# BLDC-CONNECTORS.net
KiCad netlist of a schematic drawn in Altium Designer
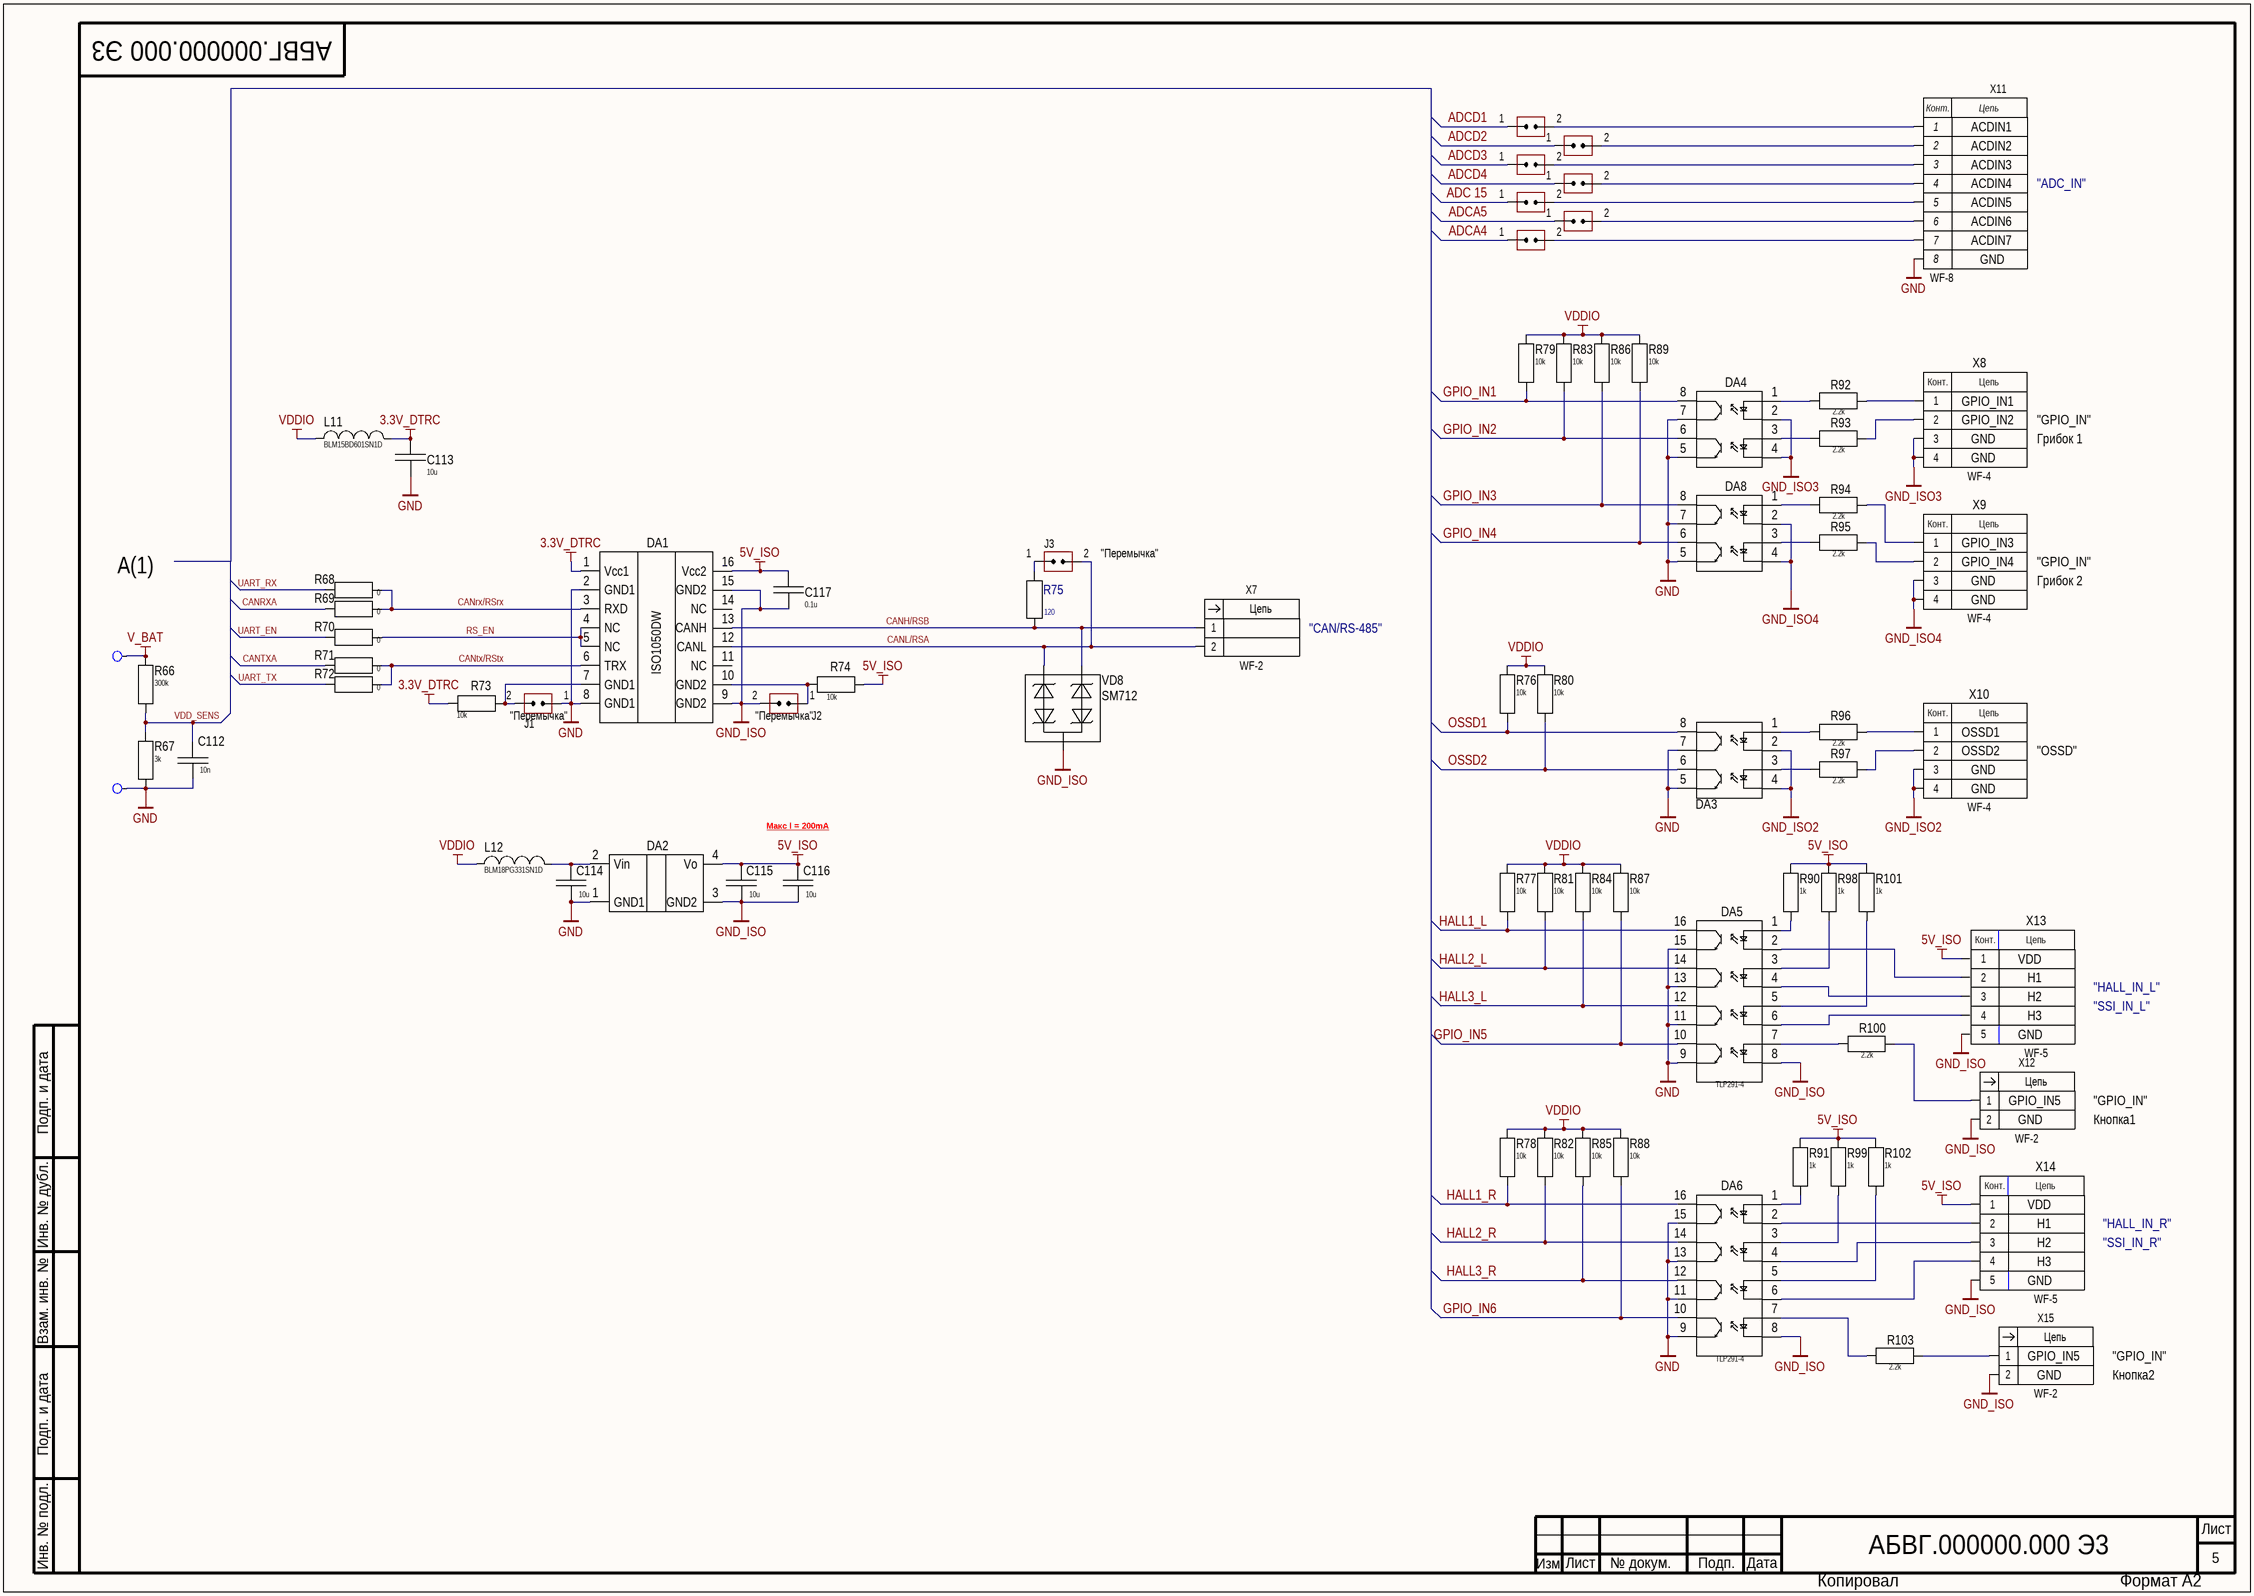
[diagram p0: BLDC-CONNECTORS.SchDoc]

(export (version "E")
  (design (tool "Eeschema 10.0.6"))
  (components
    (comp (ref "C112")
      (value "10n")
      (footprint "CAP: 0402")
      (fields
        (field (name "VOLTAGE") "10V")
        (field (name "PARTNUMBER") "C0402C104K8PAC")
        (field (name "MANUFACTURER") "Kemet")
      )
      (libsource (lib "Fider_Board_Lib") (part "CAP 0402"))
    )
    (comp (ref "C113")
      (value "10u")
      (footprint "CAP: 0402")
      (fields (field (name "VOLTAGE") "6.3V") (field (name "PARTNUMBER") "CC0402MRX5R5BB106"))
      (libsource (lib "Fider_Board_Lib") (part "CAP 0402"))
    )
    (comp (ref "C114")
      (value "10u")
      (footprint "CAP: 0402")
      (fields (field (name "VOLTAGE") "6.3V") (field (name "PARTNUMBER") "CC0402MRX5R5BB106"))
      (libsource (lib "Fider_Board_Lib") (part "CAP 0402"))
    )
    (comp (ref "C115")
      (value "10u")
      (footprint "CAP: 0402")
      (fields (field (name "VOLTAGE") "6.3V") (field (name "PARTNUMBER") "CC0402MRX5R5BB106"))
      (libsource (lib "Fider_Board_Lib") (part "CAP 0402"))
    )
    (comp (ref "C116")
      (value "10u")
      (footprint "CAP: 0402")
      (fields (field (name "VOLTAGE") "6.3V") (field (name "PARTNUMBER") "CC0402MRX5R5BB106"))
      (libsource (lib "Fider_Board_Lib") (part "CAP 0402"))
    )
    (comp (ref "C117")
      (value "0.1u")
      (footprint "CAP: 0402")
      (fields
        (field (name "VOLTAGE") "10V")
        (field (name "PARTNUMBER") "C0402C104K8PAC")
        (field (name "MANUFACTURER") "Kemet")
      )
      (libsource (lib "Fider_Board_Lib") (part "CAP 0402"))
    )
    (comp (ref "DA1")
      (value "ISO1050DW")
      (footprint "SOIC-16-300-1.27")
      (description "Isolated CAN Trcvr 5kV RMS")
      (fields (field (name "PARTNUMBER") "ISO1050DW"))
      (libsource (lib "BKM_SCH_Lib") (part "ISO1050DW"))
    )
    (comp (ref "DA2")
      (value "ROE-3.305S")
      (footprint "ROE-3.305S")
      (description "Isol DC/DC 3 to 5V 0.2A")
      (fields (field (name "PARTNUMBER") "TSR 1"))
      (libsource (lib "BKM_SCH_Lib") (part "ROE-3.305S"))
    )
    (comp (ref "DA3")
      (value "MOCD207R2M")
      (footprint "8-SOIC")
      (libsource (lib "BKM_SCH_Lib") (part "MOCD207R2M"))
    )
    (comp (ref "DA4")
      (value "MOCD207R2M")
      (footprint "8-SOIC")
      (libsource (lib "BKM_SCH_Lib") (part "MOCD207R2M"))
    )
    (comp (ref "DA5")
      (value "TLP291-4")
      (footprint "16-SO")
      (fields (field (name "PARTNUMBER") "TLP291-4(GB.E)"))
      (libsource (lib "BKM_SCH_Lib") (part "TLP291-4(GB.E)"))
    )
    (comp (ref "DA6")
      (value "TLP291-4")
      (footprint "16-SO")
      (fields (field (name "PARTNUMBER") "TLP291-4(GB.E)"))
      (libsource (lib "BKM_SCH_Lib") (part "TLP291-4(GB.E)"))
    )
    (comp (ref "DA8")
      (value "MOCD207R2M")
      (footprint "8-SOIC")
      (libsource (lib "BKM_SCH_Lib") (part "MOCD207R2M"))
    )
    (comp (ref "J1")
      (value "~")
      (footprint "CustomCase:CON: JUMPER x1")
      (fields (field (name "COMMENTTEXT") "\"Перемычка\""))
      (libsource (lib "Connector") (part "Jumper_single"))
    )
    (comp (ref "J2")
      (value "~")
      (footprint "CustomCase:CON: JUMPER x1")
      (fields (field (name "COMMENTTEXT") "\"Перемычка\""))
      (libsource (lib "Connector") (part "Jumper_single"))
    )
    (comp (ref "J3")
      (value "~")
      (footprint "CustomCase:CON: JUMPER x1")
      (fields (field (name "COMMENTTEXT") "\"Перемычка\""))
      (libsource (lib "") (part "Jumper_single_1"))
    )
    (comp (ref "J4")
      (value "~")
      (footprint "CustomCase:CON: JUMPER x1")
      (libsource (lib "") (part "Jumper_single_1"))
    )
    (comp (ref "J5")
      (value "~")
      (footprint "CustomCase:CON: JUMPER x1")
      (libsource (lib "") (part "Jumper_single_1"))
    )
    (comp (ref "J6")
      (value "~")
      (footprint "CustomCase:CON: JUMPER x1")
      (libsource (lib "") (part "Jumper_single_1"))
    )
    (comp (ref "J7")
      (value "~")
      (footprint "CustomCase:CON: JUMPER x1")
      (libsource (lib "") (part "Jumper_single_1"))
    )
    (comp (ref "J8")
      (value "~")
      (footprint "CustomCase:CON: JUMPER x1")
      (libsource (lib "") (part "Jumper_single_1"))
    )
    (comp (ref "J9")
      (value "~")
      (footprint "CustomCase:CON: JUMPER x1")
      (libsource (lib "") (part "Jumper_single_1"))
    )
    (comp (ref "J10")
      (value "~")
      (footprint "CustomCase:CON: JUMPER x1")
      (libsource (lib "") (part "Jumper_single_1"))
    )
    (comp (ref "L11")
      (value "BLM15BD601SN1D")
      (footprint "IND: 0402")
      (libsource (lib "Fider_Board_Lib") (part "BLM15BD601SN1D"))
    )
    (comp (ref "L12")
      (value "BLM18PG331SN1D")
      (footprint "IND: 0603")
      (libsource (lib "Fider_Board_Lib") (part "BLM18PG331SN1D"))
    )
    (comp (ref "R66")
      (value "300k")
      (footprint "RES: 0402")
      (fields (field (name "TOLERANCE") "1%"))
      (libsource (lib "BKM_SCH_Lib") (part "RES 0402"))
    )
    (comp (ref "R67")
      (value "3k")
      (footprint "RES: 0402")
      (fields (field (name "TOLERANCE") "1%"))
      (libsource (lib "BKM_SCH_Lib") (part "RES 0402"))
    )
    (comp (ref "R68")
      (value "0")
      (footprint "RES: 0402")
      (fields (field (name "TOLERANCE") "1%"))
      (libsource (lib "BKM_SCH_Lib") (part "RES 0402"))
    )
    (comp (ref "R69")
      (value "0")
      (footprint "RES: 0402")
      (fields (field (name "TOLERANCE") "1%"))
      (libsource (lib "BKM_SCH_Lib") (part "RES 0402"))
    )
    (comp (ref "R70")
      (value "0")
      (footprint "RES: 0402")
      (fields (field (name "TOLERANCE") "1%"))
      (libsource (lib "BKM_SCH_Lib") (part "RES 0402"))
    )
    (comp (ref "R71")
      (value "0")
      (footprint "RES: 0402")
      (fields (field (name "TOLERANCE") "1%"))
      (libsource (lib "BKM_SCH_Lib") (part "RES 0402"))
    )
    (comp (ref "R72")
      (value "0")
      (footprint "RES: 0402")
      (fields (field (name "TOLERANCE") "1%"))
      (libsource (lib "BKM_SCH_Lib") (part "RES 0402"))
    )
    (comp (ref "R73")
      (value "10k")
      (footprint "RES: 0402")
      (fields (field (name "TOLERANCE") "1%"))
      (libsource (lib "BKM_SCH_Lib") (part "RES 0402"))
    )
    (comp (ref "R74")
      (value "10k")
      (footprint "RES: 0402")
      (fields (field (name "TOLERANCE") "1%"))
      (libsource (lib "BKM_SCH_Lib") (part "RES 0402"))
    )
    (comp (ref "R75")
      (value "120")
      (footprint "RES: 0603")
      (fields (field (name "PARTNUMBER") "CRCW0603120RFKEAHP"))
      (libsource (lib "Fider_Board_Lib") (part "RES 0603"))
    )
    (comp (ref "R76")
      (value "10k")
      (footprint "RES: 0402")
      (fields (field (name "TOLERANCE") "1%"))
      (libsource (lib "BKM_SCH_Lib") (part "RES 0402"))
    )
    (comp (ref "R77")
      (value "10k")
      (footprint "RES: 0402")
      (fields (field (name "TOLERANCE") "1%"))
      (libsource (lib "BKM_SCH_Lib") (part "RES 0402"))
    )
    (comp (ref "R78")
      (value "10k")
      (footprint "RES: 0402")
      (fields (field (name "TOLERANCE") "1%"))
      (libsource (lib "BKM_SCH_Lib") (part "RES 0402"))
    )
    (comp (ref "R79")
      (value "10k")
      (footprint "RES: 0402")
      (fields (field (name "TOLERANCE") "1%"))
      (libsource (lib "BKM_SCH_Lib") (part "RES 0402"))
    )
    (comp (ref "R80")
      (value "10k")
      (footprint "RES: 0402")
      (fields (field (name "TOLERANCE") "1%"))
      (libsource (lib "BKM_SCH_Lib") (part "RES 0402"))
    )
    (comp (ref "R81")
      (value "10k")
      (footprint "RES: 0402")
      (fields (field (name "TOLERANCE") "1%"))
      (libsource (lib "BKM_SCH_Lib") (part "RES 0402"))
    )
    (comp (ref "R82")
      (value "10k")
      (footprint "RES: 0402")
      (fields (field (name "TOLERANCE") "1%"))
      (libsource (lib "BKM_SCH_Lib") (part "RES 0402"))
    )
    (comp (ref "R83")
      (value "10k")
      (footprint "RES: 0402")
      (fields (field (name "TOLERANCE") "1%"))
      (libsource (lib "BKM_SCH_Lib") (part "RES 0402"))
    )
    (comp (ref "R84")
      (value "10k")
      (footprint "RES: 0402")
      (fields (field (name "TOLERANCE") "1%"))
      (libsource (lib "BKM_SCH_Lib") (part "RES 0402"))
    )
    (comp (ref "R85")
      (value "10k")
      (footprint "RES: 0402")
      (fields (field (name "TOLERANCE") "1%"))
      (libsource (lib "BKM_SCH_Lib") (part "RES 0402"))
    )
    (comp (ref "R86")
      (value "10k")
      (footprint "RES: 0402")
      (fields (field (name "TOLERANCE") "1%"))
      (libsource (lib "BKM_SCH_Lib") (part "RES 0402"))
    )
    (comp (ref "R87")
      (value "10k")
      (footprint "RES: 0402")
      (fields (field (name "TOLERANCE") "1%"))
      (libsource (lib "BKM_SCH_Lib") (part "RES 0402"))
    )
    (comp (ref "R88")
      (value "10k")
      (footprint "RES: 0402")
      (fields (field (name "TOLERANCE") "1%"))
      (libsource (lib "BKM_SCH_Lib") (part "RES 0402"))
    )
    (comp (ref "R89")
      (value "10k")
      (footprint "RES: 0402")
      (fields (field (name "TOLERANCE") "1%"))
      (libsource (lib "BKM_SCH_Lib") (part "RES 0402"))
    )
    (comp (ref "R90")
      (value "1k")
      (footprint "RES: 0402")
      (fields (field (name "TOLERANCE") "1%"))
      (libsource (lib "BKM_SCH_Lib") (part "RES 0402"))
    )
    (comp (ref "R91")
      (value "1k")
      (footprint "RES: 0402")
      (fields (field (name "TOLERANCE") "1%"))
      (libsource (lib "BKM_SCH_Lib") (part "RES 0402"))
    )
    (comp (ref "R92")
      (value "2.2k")
      (footprint "RES: 0402")
      (fields (field (name "TOLERANCE") "1%"))
      (libsource (lib "BKM_SCH_Lib") (part "RES 0402"))
    )
    (comp (ref "R93")
      (value "2.2k")
      (footprint "RES: 0402")
      (fields (field (name "TOLERANCE") "1%"))
      (libsource (lib "BKM_SCH_Lib") (part "RES 0402"))
    )
    (comp (ref "R94")
      (value "2.2k")
      (footprint "RES: 0402")
      (fields (field (name "TOLERANCE") "1%"))
      (libsource (lib "BKM_SCH_Lib") (part "RES 0402"))
    )
    (comp (ref "R95")
      (value "2.2k")
      (footprint "RES: 0402")
      (fields (field (name "TOLERANCE") "1%"))
      (libsource (lib "BKM_SCH_Lib") (part "RES 0402"))
    )
    (comp (ref "R96")
      (value "2.2k")
      (footprint "RES: 0402")
      (fields (field (name "TOLERANCE") "1%"))
      (libsource (lib "BKM_SCH_Lib") (part "RES 0402"))
    )
    (comp (ref "R97")
      (value "2.2k")
      (footprint "RES: 0402")
      (fields (field (name "TOLERANCE") "1%"))
      (libsource (lib "BKM_SCH_Lib") (part "RES 0402"))
    )
    (comp (ref "R98")
      (value "1k")
      (footprint "RES: 0402")
      (fields (field (name "TOLERANCE") "1%"))
      (libsource (lib "BKM_SCH_Lib") (part "RES 0402"))
    )
    (comp (ref "R99")
      (value "1k")
      (footprint "RES: 0402")
      (fields (field (name "TOLERANCE") "1%"))
      (libsource (lib "BKM_SCH_Lib") (part "RES 0402"))
    )
    (comp (ref "R100")
      (value "2.2k")
      (footprint "RES: 0402")
      (fields (field (name "TOLERANCE") "1%"))
      (libsource (lib "BKM_SCH_Lib") (part "RES 0402"))
    )
    (comp (ref "R101")
      (value "1k")
      (footprint "RES: 0402")
      (fields (field (name "TOLERANCE") "1%"))
      (libsource (lib "BKM_SCH_Lib") (part "RES 0402"))
    )
    (comp (ref "R102")
      (value "1k")
      (footprint "RES: 0402")
      (fields (field (name "TOLERANCE") "1%"))
      (libsource (lib "BKM_SCH_Lib") (part "RES 0402"))
    )
    (comp (ref "R103")
      (value "2.2k")
      (footprint "RES: 0402")
      (fields (field (name "TOLERANCE") "1%"))
      (libsource (lib "BKM_SCH_Lib") (part "RES 0402"))
    )
    (comp (ref "T1")
      (value "TestPoint PWR")
      (footprint "CON: DJ617-6.3 (TA-MR1)")
      (libsource (lib "BKM_SCH_Lib") (part "TestPoint PWR"))
    )
    (comp (ref "T2")
      (value "TestPoint PWR")
      (footprint "CON: DJ617-6.3 (TA-MR1)")
      (libsource (lib "BKM_SCH_Lib") (part "TestPoint PWR"))
    )
    (comp (ref "VD8")
      (value "SM712")
      (footprint "SOT-23-3")
      (fields (field (name "PARTNUMBER") "SM712-02HTG"))
      (libsource (lib "Fider_Board_Lib") (part "SM712"))
    )
    (comp (ref "X7")
      (value "WF-2")
      (footprint "WF-2")
      (fields (field (name "PARTNUMBER") "Вилка WF-2 «Zhenqin»"))
      (libsource (lib "connectors") (part "WF-2"))
    )
    (comp (ref "X8") (value "WF-4") (footprint "WF-4") (libsource (lib "connectors") (part "WF-4_T")))
    (comp (ref "X9") (value "WF-4") (footprint "WF-4") (libsource (lib "connectors") (part "WF-4_T")))
    (comp (ref "X10") (value "WF-4") (footprint "WF-4") (libsource (lib "connectors") (part "WF-4_T")))
    (comp (ref "X11")
      (value "WF-8")
      (footprint "WF-8")
      (fields (field (name "PARTNUMBER") "Вилка WF-8 «Zhenqin»"))
      (libsource (lib "connectors") (part "WF-8"))
    )
    (comp (ref "X12")
      (value "WF-2")
      (footprint "WF-2")
      (fields (field (name "PARTNUMBER") "Вилка WF-2 «Zhenqin»"))
      (libsource (lib "connectors") (part "WF-2"))
    )
    (comp (ref "X13")
      (value "WF-5")
      (footprint "WF-5")
      (fields (field (name "PARTNUMBER") "Вилка WF-5 «Zhenqin»"))
      (libsource (lib "connectors") (part "WF-5"))
    )
    (comp (ref "X14")
      (value "WF-5")
      (footprint "WF-5")
      (fields (field (name "PARTNUMBER") "Вилка WF-5 «Zhenqin»"))
      (libsource (lib "connectors") (part "WF-5"))
    )
    (comp (ref "X15")
      (value "WF-2")
      (footprint "WF-2")
      (fields (field (name "PARTNUMBER") "Вилка WF-2 «Zhenqin»"))
      (libsource (lib "connectors") (part "WF-2"))
    )
  )
  (nets
    (net (code "1") (name "/ADC 15") (class "Default")
      (node (ref "J6") (pin "1") (pinfunction "IN_1") (pintype "passive"))
    )
    (net (code "2") (name "/ADCA4") (class "Default")
      (node (ref "J7") (pin "1") (pinfunction "IN_1") (pintype "passive"))
    )
    (net (code "3") (name "/ADCA5") (class "Default")
      (node (ref "J10") (pin "1") (pinfunction "IN_1") (pintype "passive"))
    )
    (net (code "4") (name "/ADCD1") (class "Default")
      (node (ref "J4") (pin "1") (pinfunction "IN_1") (pintype "passive"))
    )
    (net (code "5") (name "/ADCD2") (class "Default")
      (node (ref "J8") (pin "1") (pinfunction "IN_1") (pintype "passive"))
    )
    (net (code "6") (name "/ADCD3") (class "Default")
      (node (ref "J5") (pin "1") (pinfunction "IN_1") (pintype "passive"))
    )
    (net (code "7") (name "/ADCD4") (class "Default")
      (node (ref "J9") (pin "1") (pinfunction "IN_1") (pintype "passive"))
    )
    (net (code "8") (name "/CANH{slash}RSB") (class "Default")
      (node (ref "DA1") (pin "13") (pinfunction "CANH_13") (pintype "passive"))
      (node (ref "R75") (pin "1") (pinfunction "1_1") (pintype "passive"))
      (node (ref "VD8") (pin "1") (pinfunction "1_1") (pintype "passive"))
      (node (ref "X7") (pin "1") (pinfunction "1_1") (pintype "passive"))
    )
    (net (code "9") (name "/CANL{slash}RSA") (class "Default")
      (node (ref "DA1") (pin "12") (pinfunction "CANL_12") (pintype "passive"))
      (node (ref "J3") (pin "2") (pinfunction "IN_2") (pintype "passive"))
      (node (ref "VD8") (pin "2") (pinfunction "2_2") (pintype "passive"))
      (node (ref "X7") (pin "2") (pinfunction "2_2") (pintype "passive"))
    )
    (net (code "10") (name "/CANRXA") (class "Default")
      (node (ref "R69") (pin "1") (pinfunction "1_1") (pintype "passive"))
    )
    (net (code "11") (name "/CANTXA") (class "Default")
      (node (ref "R71") (pin "1") (pinfunction "1_1") (pintype "passive"))
    )
    (net (code "12") (name "/CANrx{slash}RSrx") (class "Default")
      (node (ref "DA1") (pin "3") (pinfunction "RXD_3") (pintype "passive"))
      (node (ref "R68") (pin "2") (pinfunction "2_2") (pintype "passive"))
      (node (ref "R69") (pin "2") (pinfunction "2_2") (pintype "passive"))
    )
    (net (code "13") (name "/CANtx{slash}RStx") (class "Default")
      (node (ref "DA1") (pin "6") (pinfunction "TRX_6") (pintype "passive"))
      (node (ref "R71") (pin "2") (pinfunction "2_2") (pintype "passive"))
      (node (ref "R72") (pin "2") (pinfunction "2_2") (pintype "passive"))
    )
    (net (code "14") (name "/GPIO_IN1") (class "Default")
      (node (ref "DA4") (pin "8") (pinfunction "Vdd_8") (pintype "passive"))
      (node (ref "R79") (pin "2") (pinfunction "2_2") (pintype "passive"))
    )
    (net (code "15") (name "/GPIO_IN2") (class "Default")
      (node (ref "DA4") (pin "6") (pinfunction "Vdd_6") (pintype "passive"))
      (node (ref "R83") (pin "2") (pinfunction "2_2") (pintype "passive"))
    )
    (net (code "16") (name "/GPIO_IN3") (class "Default")
      (node (ref "DA8") (pin "8") (pinfunction "Vdd_8") (pintype "passive"))
      (node (ref "R86") (pin "2") (pinfunction "2_2") (pintype "passive"))
    )
    (net (code "17") (name "/GPIO_IN4") (class "Default")
      (node (ref "DA8") (pin "6") (pinfunction "Vdd_6") (pintype "passive"))
      (node (ref "R89") (pin "2") (pinfunction "2_2") (pintype "passive"))
    )
    (net (code "18") (name "/GPIO_IN5") (class "Default")
      (node (ref "DA5") (pin "10") (pinfunction "Vdd_10") (pintype "passive"))
      (node (ref "R87") (pin "2") (pinfunction "2_2") (pintype "passive"))
    )
    (net (code "19") (name "/GPIO_IN6") (class "Default")
      (node (ref "DA6") (pin "10") (pinfunction "Vdd_10") (pintype "passive"))
      (node (ref "R88") (pin "2") (pinfunction "2_2") (pintype "passive"))
    )
    (net (code "20") (name "/HALL1_L") (class "Default")
      (node (ref "DA5") (pin "16") (pinfunction "Vdd_16") (pintype "passive"))
      (node (ref "R77") (pin "2") (pinfunction "2_2") (pintype "passive"))
    )
    (net (code "21") (name "/HALL1_R") (class "Default")
      (node (ref "DA6") (pin "16") (pinfunction "Vdd_16") (pintype "passive"))
      (node (ref "R78") (pin "2") (pinfunction "2_2") (pintype "passive"))
    )
    (net (code "22") (name "/HALL2_L") (class "Default")
      (node (ref "DA5") (pin "14") (pinfunction "Vdd_14") (pintype "passive"))
      (node (ref "R81") (pin "2") (pinfunction "2_2") (pintype "passive"))
    )
    (net (code "23") (name "/HALL2_R") (class "Default")
      (node (ref "DA6") (pin "14") (pinfunction "Vdd_14") (pintype "passive"))
      (node (ref "R82") (pin "2") (pinfunction "2_2") (pintype "passive"))
    )
    (net (code "24") (name "/HALL3_L") (class "Default")
      (node (ref "DA5") (pin "12") (pinfunction "Vdd_12") (pintype "passive"))
      (node (ref "R84") (pin "2") (pinfunction "2_2") (pintype "passive"))
    )
    (net (code "25") (name "/HALL3_R") (class "Default")
      (node (ref "DA6") (pin "12") (pinfunction "Vdd_12") (pintype "passive"))
      (node (ref "R85") (pin "2") (pinfunction "2_2") (pintype "passive"))
    )
    (net (code "26") (name "/OSSD1") (class "Default")
      (node (ref "DA3") (pin "8") (pinfunction "Vdd_8") (pintype "passive"))
      (node (ref "R76") (pin "2") (pinfunction "2_2") (pintype "passive"))
    )
    (net (code "27") (name "/OSSD2") (class "Default")
      (node (ref "DA3") (pin "6") (pinfunction "Vdd_6") (pintype "passive"))
      (node (ref "R80") (pin "2") (pinfunction "2_2") (pintype "passive"))
    )
    (net (code "28") (name "/RS_EN") (class "Default")
      (node (ref "DA1") (pin "4") (pinfunction "NC_4") (pintype "passive"))
      (node (ref "DA1") (pin "5") (pinfunction "NC_5") (pintype "passive"))
      (node (ref "R70") (pin "2") (pinfunction "2_2") (pintype "passive"))
    )
    (net (code "29") (name "/UART_EN") (class "Default")
      (node (ref "R70") (pin "1") (pinfunction "1_1") (pintype "passive"))
    )
    (net (code "30") (name "/UART_RX") (class "Default")
      (node (ref "R68") (pin "1") (pinfunction "1_1") (pintype "passive"))
    )
    (net (code "31") (name "/UART_TX") (class "Default")
      (node (ref "R72") (pin "1") (pinfunction "1_1") (pintype "passive"))
    )
    (net (code "32") (name "/VDD_SENS") (class "Default")
      (node (ref "C112") (pin "2") (pinfunction "2_2") (pintype "passive"))
      (node (ref "R66") (pin "2") (pinfunction "2_2") (pintype "passive"))
      (node (ref "R67") (pin "1") (pinfunction "1_1") (pintype "passive"))
    )
    (net (code "33") (name "3.3V_DTRC") (class "Default")
      (node (ref "C113") (pin "2") (pinfunction "2_2") (pintype "passive"))
      (node (ref "DA1") (pin "1") (pinfunction "Vcc1_1") (pintype "passive"))
      (node (ref "L11") (pin "1") (pinfunction "1_1") (pintype "passive"))
      (node (ref "R73") (pin "1") (pinfunction "1_1") (pintype "passive"))
    )
    (net (code "34") (name "5V_ISO") (class "Default")
      (node (ref "C115") (pin "2") (pinfunction "2_2") (pintype "passive"))
      (node (ref "C116") (pin "2") (pinfunction "2_2") (pintype "passive"))
      (node (ref "C117") (pin "2") (pinfunction "2_2") (pintype "passive"))
      (node (ref "DA1") (pin "16") (pinfunction "Vcc2_16") (pintype "passive"))
      (node (ref "DA2") (pin "4") (pinfunction "Vo_4") (pintype "passive"))
      (node (ref "R101") (pin "1") (pinfunction "1_1") (pintype "passive"))
      (node (ref "R102") (pin "1") (pinfunction "1_1") (pintype "passive"))
      (node (ref "R74") (pin "2") (pinfunction "2_2") (pintype "passive"))
      (node (ref "R90") (pin "1") (pinfunction "1_1") (pintype "passive"))
      (node (ref "R91") (pin "1") (pinfunction "1_1") (pintype "passive"))
      (node (ref "R98") (pin "1") (pinfunction "1_1") (pintype "passive"))
      (node (ref "R99") (pin "1") (pinfunction "1_1") (pintype "passive"))
      (node (ref "X13") (pin "1") (pinfunction "1_1") (pintype "passive"))
      (node (ref "X14") (pin "1") (pinfunction "1_1") (pintype "passive"))
    )
    (net (code "35") (name "GND") (class "Default")
      (node (ref "C112") (pin "1") (pinfunction "1_1") (pintype "passive"))
      (node (ref "C113") (pin "1") (pinfunction "1_1") (pintype "passive"))
      (node (ref "C114") (pin "1") (pinfunction "1_1") (pintype "passive"))
      (node (ref "DA1") (pin "2") (pinfunction "GND1_2") (pintype "passive"))
      (node (ref "DA1") (pin "8") (pinfunction "GND1_8") (pintype "passive"))
      (node (ref "DA2") (pin "1") (pinfunction "GND1_1") (pintype "passive"))
      (node (ref "DA3") (pin "5") (pinfunction "Vo1_5") (pintype "passive"))
      (node (ref "DA3") (pin "7") (pinfunction "Vo1_7") (pintype "passive"))
      (node (ref "DA4") (pin "5") (pinfunction "Vo1_5") (pintype "passive"))
      (node (ref "DA4") (pin "7") (pinfunction "Vo1_7") (pintype "passive"))
      (node (ref "DA5") (pin "11") (pinfunction "Vo1_11") (pintype "passive"))
      (node (ref "DA5") (pin "13") (pinfunction "Vo1_13") (pintype "passive"))
      (node (ref "DA5") (pin "15") (pinfunction "Vo1_15") (pintype "passive"))
      (node (ref "DA5") (pin "9") (pinfunction "Vo1_9") (pintype "passive"))
      (node (ref "DA6") (pin "11") (pinfunction "Vo1_11") (pintype "passive"))
      (node (ref "DA6") (pin "13") (pinfunction "Vo1_13") (pintype "passive"))
      (node (ref "DA6") (pin "15") (pinfunction "Vo1_15") (pintype "passive"))
      (node (ref "DA6") (pin "9") (pinfunction "Vo1_9") (pintype "passive"))
      (node (ref "DA8") (pin "5") (pinfunction "Vo1_5") (pintype "passive"))
      (node (ref "DA8") (pin "7") (pinfunction "Vo1_7") (pintype "passive"))
      (node (ref "J1") (pin "1") (pinfunction "IN_1") (pintype "passive"))
      (node (ref "R67") (pin "2") (pinfunction "2_2") (pintype "passive"))
      (node (ref "T2") (pin "1") (pinfunction "T_1") (pintype "passive"))
      (node (ref "X11") (pin "8") (pinfunction "8_8") (pintype "passive"))
    )
    (net (code "36") (name "GND_ISO") (class "Default")
      (node (ref "C115") (pin "1") (pinfunction "1_1") (pintype "passive"))
      (node (ref "C116") (pin "1") (pinfunction "1_1") (pintype "passive"))
      (node (ref "C117") (pin "1") (pinfunction "1_1") (pintype "passive"))
      (node (ref "DA1") (pin "15") (pinfunction "GND2_15") (pintype "passive"))
      (node (ref "DA1") (pin "9") (pinfunction "GND2_9") (pintype "passive"))
      (node (ref "DA2") (pin "3") (pinfunction "GND2_3") (pintype "passive"))
      (node (ref "DA5") (pin "8") (pinfunction "C1_8") (pintype "passive"))
      (node (ref "DA6") (pin "8") (pinfunction "C1_8") (pintype "passive"))
      (node (ref "J2") (pin "2") (pinfunction "IN_2") (pintype "passive"))
      (node (ref "VD8") (pin "3") (pinfunction "3_3") (pintype "passive"))
      (node (ref "X12") (pin "2") (pinfunction "2_2") (pintype "passive"))
      (node (ref "X13") (pin "5") (pinfunction "5_5") (pintype "passive"))
      (node (ref "X14") (pin "5") (pinfunction "5_5") (pintype "passive"))
      (node (ref "X15") (pin "2") (pinfunction "2_2") (pintype "passive"))
    )
    (net (code "37") (name "GND_ISO2") (class "Default")
      (node (ref "DA3") (pin "2") (pinfunction "C1_2") (pintype "passive"))
      (node (ref "DA3") (pin "4") (pinfunction "C1_4") (pintype "passive"))
      (node (ref "X10") (pin "3") (pinfunction "3_3") (pintype "passive"))
      (node (ref "X10") (pin "4") (pinfunction "4_4") (pintype "passive"))
    )
    (net (code "38") (name "GND_ISO3") (class "Default")
      (node (ref "DA4") (pin "2") (pinfunction "C1_2") (pintype "passive"))
      (node (ref "DA4") (pin "4") (pinfunction "C1_4") (pintype "passive"))
      (node (ref "X8") (pin "3") (pinfunction "3_3") (pintype "passive"))
      (node (ref "X8") (pin "4") (pinfunction "4_4") (pintype "passive"))
    )
    (net (code "39") (name "GND_ISO4") (class "Default")
      (node (ref "DA8") (pin "2") (pinfunction "C1_2") (pintype "passive"))
      (node (ref "DA8") (pin "4") (pinfunction "C1_4") (pintype "passive"))
      (node (ref "X9") (pin "3") (pinfunction "3_3") (pintype "passive"))
      (node (ref "X9") (pin "4") (pinfunction "4_4") (pintype "passive"))
    )
    (net (code "40") (name "Net-(DA1-GND1-Pad7)") (class "Default")
      (node (ref "DA1") (pin "7") (pinfunction "GND1_7") (pintype "passive"))
      (node (ref "J1") (pin "2") (pinfunction "IN_2") (pintype "passive"))
      (node (ref "R73") (pin "2") (pinfunction "2_2") (pintype "passive"))
    )
    (net (code "41") (name "Net-(DA1-GND2-Pad10)") (class "Default")
      (node (ref "DA1") (pin "10") (pinfunction "GND2_10") (pintype "passive"))
      (node (ref "J2") (pin "1") (pinfunction "IN_1") (pintype "passive"))
      (node (ref "R74") (pin "1") (pinfunction "1_1") (pintype "passive"))
    )
    (net (code "42") (name "Net-(DA2-Vin)") (class "Default")
      (node (ref "C114") (pin "2") (pinfunction "2_2") (pintype "passive"))
      (node (ref "DA2") (pin "2") (pinfunction "Vin_2") (pintype "passive"))
      (node (ref "L12") (pin "2") (pinfunction "2_2") (pintype "passive"))
    )
    (net (code "43") (name "Net-(DA3-A1-Pad1)") (class "Default")
      (node (ref "DA3") (pin "1") (pinfunction "A1_1") (pintype "passive"))
      (node (ref "R96") (pin "1") (pinfunction "1_1") (pintype "passive"))
    )
    (net (code "44") (name "Net-(DA3-A1-Pad3)") (class "Default")
      (node (ref "DA3") (pin "3") (pinfunction "A1_3") (pintype "passive"))
      (node (ref "R97") (pin "1") (pinfunction "1_1") (pintype "passive"))
    )
    (net (code "45") (name "Net-(DA4-A1-Pad1)") (class "Default")
      (node (ref "DA4") (pin "1") (pinfunction "A1_1") (pintype "passive"))
      (node (ref "R92") (pin "1") (pinfunction "1_1") (pintype "passive"))
    )
    (net (code "46") (name "Net-(DA4-A1-Pad3)") (class "Default")
      (node (ref "DA4") (pin "3") (pinfunction "A1_3") (pintype "passive"))
      (node (ref "R93") (pin "1") (pinfunction "1_1") (pintype "passive"))
    )
    (net (code "47") (name "Net-(DA5-A1-Pad1)") (class "Default")
      (node (ref "DA5") (pin "1") (pinfunction "A1_1") (pintype "passive"))
      (node (ref "R90") (pin "2") (pinfunction "2_2") (pintype "passive"))
    )
    (net (code "48") (name "Net-(DA5-A1-Pad3)") (class "Default")
      (node (ref "DA5") (pin "3") (pinfunction "A1_3") (pintype "passive"))
      (node (ref "R98") (pin "2") (pinfunction "2_2") (pintype "passive"))
    )
    (net (code "49") (name "Net-(DA5-A1-Pad5)") (class "Default")
      (node (ref "DA5") (pin "5") (pinfunction "A1_5") (pintype "passive"))
      (node (ref "R101") (pin "2") (pinfunction "2_2") (pintype "passive"))
    )
    (net (code "50") (name "Net-(DA5-A1-Pad7)") (class "Default")
      (node (ref "DA5") (pin "7") (pinfunction "A1_7") (pintype "passive"))
      (node (ref "R100") (pin "1") (pinfunction "1_1") (pintype "passive"))
    )
    (net (code "51") (name "Net-(DA5-C1-Pad2)") (class "Default")
      (node (ref "DA5") (pin "2") (pinfunction "C1_2") (pintype "passive"))
      (node (ref "X13") (pin "2") (pinfunction "2_2") (pintype "passive"))
    )
    (net (code "52") (name "Net-(DA5-C1-Pad4)") (class "Default")
      (node (ref "DA5") (pin "4") (pinfunction "C1_4") (pintype "passive"))
      (node (ref "X13") (pin "3") (pinfunction "3_3") (pintype "passive"))
    )
    (net (code "53") (name "Net-(DA5-C1-Pad6)") (class "Default")
      (node (ref "DA5") (pin "6") (pinfunction "C1_6") (pintype "passive"))
      (node (ref "X13") (pin "4") (pinfunction "4_4") (pintype "passive"))
    )
    (net (code "54") (name "Net-(DA6-A1-Pad1)") (class "Default")
      (node (ref "DA6") (pin "1") (pinfunction "A1_1") (pintype "passive"))
      (node (ref "R91") (pin "2") (pinfunction "2_2") (pintype "passive"))
    )
    (net (code "55") (name "Net-(DA6-A1-Pad3)") (class "Default")
      (node (ref "DA6") (pin "3") (pinfunction "A1_3") (pintype "passive"))
      (node (ref "R99") (pin "2") (pinfunction "2_2") (pintype "passive"))
    )
    (net (code "56") (name "Net-(DA6-A1-Pad5)") (class "Default")
      (node (ref "DA6") (pin "5") (pinfunction "A1_5") (pintype "passive"))
      (node (ref "R102") (pin "2") (pinfunction "2_2") (pintype "passive"))
    )
    (net (code "57") (name "Net-(DA6-A1-Pad7)") (class "Default")
      (node (ref "DA6") (pin "7") (pinfunction "A1_7") (pintype "passive"))
      (node (ref "R103") (pin "1") (pinfunction "1_1") (pintype "passive"))
    )
    (net (code "58") (name "Net-(DA6-C1-Pad2)") (class "Default")
      (node (ref "DA6") (pin "2") (pinfunction "C1_2") (pintype "passive"))
      (node (ref "X14") (pin "2") (pinfunction "2_2") (pintype "passive"))
    )
    (net (code "59") (name "Net-(DA6-C1-Pad4)") (class "Default")
      (node (ref "DA6") (pin "4") (pinfunction "C1_4") (pintype "passive"))
      (node (ref "X14") (pin "3") (pinfunction "3_3") (pintype "passive"))
    )
    (net (code "60") (name "Net-(DA6-C1-Pad6)") (class "Default")
      (node (ref "DA6") (pin "6") (pinfunction "C1_6") (pintype "passive"))
      (node (ref "X14") (pin "4") (pinfunction "4_4") (pintype "passive"))
    )
    (net (code "61") (name "Net-(DA8-A1-Pad1)") (class "Default")
      (node (ref "DA8") (pin "1") (pinfunction "A1_1") (pintype "passive"))
      (node (ref "R94") (pin "1") (pinfunction "1_1") (pintype "passive"))
    )
    (net (code "62") (name "Net-(DA8-A1-Pad3)") (class "Default")
      (node (ref "DA8") (pin "3") (pinfunction "A1_3") (pintype "passive"))
      (node (ref "R95") (pin "1") (pinfunction "1_1") (pintype "passive"))
    )
    (net (code "63") (name "Net-(J3-IN-Pad1)") (class "Default")
      (node (ref "J3") (pin "1") (pinfunction "IN_1") (pintype "passive"))
      (node (ref "R75") (pin "2") (pinfunction "2_2") (pintype "passive"))
    )
    (net (code "64") (name "Net-(J4-IN-Pad2)") (class "Default")
      (node (ref "J4") (pin "2") (pinfunction "IN_2") (pintype "passive"))
      (node (ref "X11") (pin "1") (pinfunction "1_1") (pintype "passive"))
    )
    (net (code "65") (name "Net-(J5-IN-Pad2)") (class "Default")
      (node (ref "J5") (pin "2") (pinfunction "IN_2") (pintype "passive"))
      (node (ref "X11") (pin "3") (pinfunction "3_3") (pintype "passive"))
    )
    (net (code "66") (name "Net-(J6-IN-Pad2)") (class "Default")
      (node (ref "J6") (pin "2") (pinfunction "IN_2") (pintype "passive"))
      (node (ref "X11") (pin "5") (pinfunction "5_5") (pintype "passive"))
    )
    (net (code "67") (name "Net-(J7-IN-Pad2)") (class "Default")
      (node (ref "J7") (pin "2") (pinfunction "IN_2") (pintype "passive"))
      (node (ref "X11") (pin "7") (pinfunction "7_7") (pintype "passive"))
    )
    (net (code "68") (name "Net-(J8-IN-Pad2)") (class "Default")
      (node (ref "J8") (pin "2") (pinfunction "IN_2") (pintype "passive"))
      (node (ref "X11") (pin "2") (pinfunction "2_2") (pintype "passive"))
    )
    (net (code "69") (name "Net-(J9-IN-Pad2)") (class "Default")
      (node (ref "J9") (pin "2") (pinfunction "IN_2") (pintype "passive"))
      (node (ref "X11") (pin "4") (pinfunction "4_4") (pintype "passive"))
    )
    (net (code "70") (name "Net-(J10-IN-Pad2)") (class "Default")
      (node (ref "J10") (pin "2") (pinfunction "IN_2") (pintype "passive"))
      (node (ref "X11") (pin "6") (pinfunction "6_6") (pintype "passive"))
    )
    (net (code "71") (name "Net-(R92-Pad2)") (class "Default")
      (node (ref "R92") (pin "2") (pinfunction "2_2") (pintype "passive"))
      (node (ref "X8") (pin "1") (pinfunction "1_1") (pintype "passive"))
    )
    (net (code "72") (name "Net-(R93-Pad2)") (class "Default")
      (node (ref "R93") (pin "2") (pinfunction "2_2") (pintype "passive"))
      (node (ref "X8") (pin "2") (pinfunction "2_2") (pintype "passive"))
    )
    (net (code "73") (name "Net-(R94-Pad2)") (class "Default")
      (node (ref "R94") (pin "2") (pinfunction "2_2") (pintype "passive"))
      (node (ref "X9") (pin "1") (pinfunction "1_1") (pintype "passive"))
    )
    (net (code "74") (name "Net-(R95-Pad2)") (class "Default")
      (node (ref "R95") (pin "2") (pinfunction "2_2") (pintype "passive"))
      (node (ref "X9") (pin "2") (pinfunction "2_2") (pintype "passive"))
    )
    (net (code "75") (name "Net-(R96-Pad2)") (class "Default")
      (node (ref "R96") (pin "2") (pinfunction "2_2") (pintype "passive"))
      (node (ref "X10") (pin "1") (pinfunction "1_1") (pintype "passive"))
    )
    (net (code "76") (name "Net-(R97-Pad2)") (class "Default")
      (node (ref "R97") (pin "2") (pinfunction "2_2") (pintype "passive"))
      (node (ref "X10") (pin "2") (pinfunction "2_2") (pintype "passive"))
    )
    (net (code "77") (name "Net-(R100-Pad2)") (class "Default")
      (node (ref "R100") (pin "2") (pinfunction "2_2") (pintype "passive"))
      (node (ref "X12") (pin "1") (pinfunction "1_1") (pintype "passive"))
    )
    (net (code "78") (name "Net-(R103-Pad2)") (class "Default")
      (node (ref "R103") (pin "2") (pinfunction "2_2") (pintype "passive"))
      (node (ref "X15") (pin "1") (pinfunction "1_1") (pintype "passive"))
    )
    (net (code "79") (name "VDDIO") (class "Default")
      (node (ref "L11") (pin "2") (pinfunction "2_2") (pintype "passive"))
      (node (ref "L12") (pin "1") (pinfunction "1_1") (pintype "passive"))
      (node (ref "R76") (pin "1") (pinfunction "1_1") (pintype "passive"))
      (node (ref "R77") (pin "1") (pinfunction "1_1") (pintype "passive"))
      (node (ref "R78") (pin "1") (pinfunction "1_1") (pintype "passive"))
      (node (ref "R79") (pin "1") (pinfunction "1_1") (pintype "passive"))
      (node (ref "R80") (pin "1") (pinfunction "1_1") (pintype "passive"))
      (node (ref "R81") (pin "1") (pinfunction "1_1") (pintype "passive"))
      (node (ref "R82") (pin "1") (pinfunction "1_1") (pintype "passive"))
      (node (ref "R83") (pin "1") (pinfunction "1_1") (pintype "passive"))
      (node (ref "R84") (pin "1") (pinfunction "1_1") (pintype "passive"))
      (node (ref "R85") (pin "1") (pinfunction "1_1") (pintype "passive"))
      (node (ref "R86") (pin "1") (pinfunction "1_1") (pintype "passive"))
      (node (ref "R87") (pin "1") (pinfunction "1_1") (pintype "passive"))
      (node (ref "R88") (pin "1") (pinfunction "1_1") (pintype "passive"))
      (node (ref "R89") (pin "1") (pinfunction "1_1") (pintype "passive"))
    )
    (net (code "80") (name "V_BAT") (class "Default")
      (node (ref "R66") (pin "1") (pinfunction "1_1") (pintype "passive"))
      (node (ref "T1") (pin "1") (pinfunction "T_1") (pintype "passive"))
    )
    (net (code "81") (name "unconnected-(DA1-NC-Pad11)") (class "Default")
      (node (ref "DA1") (pin "11") (pinfunction "NC_11") (pintype "passive"))
    )
    (net (code "82") (name "unconnected-(DA1-NC-Pad14)") (class "Default")
      (node (ref "DA1") (pin "14") (pinfunction "NC_14") (pintype "passive"))
    )
  )
)
